# ProPrj_ftdi-jtag-xilinx_2025-03-20_v3_1.net
KiCad netlist of a schematic drawn in EasyEDA Pro
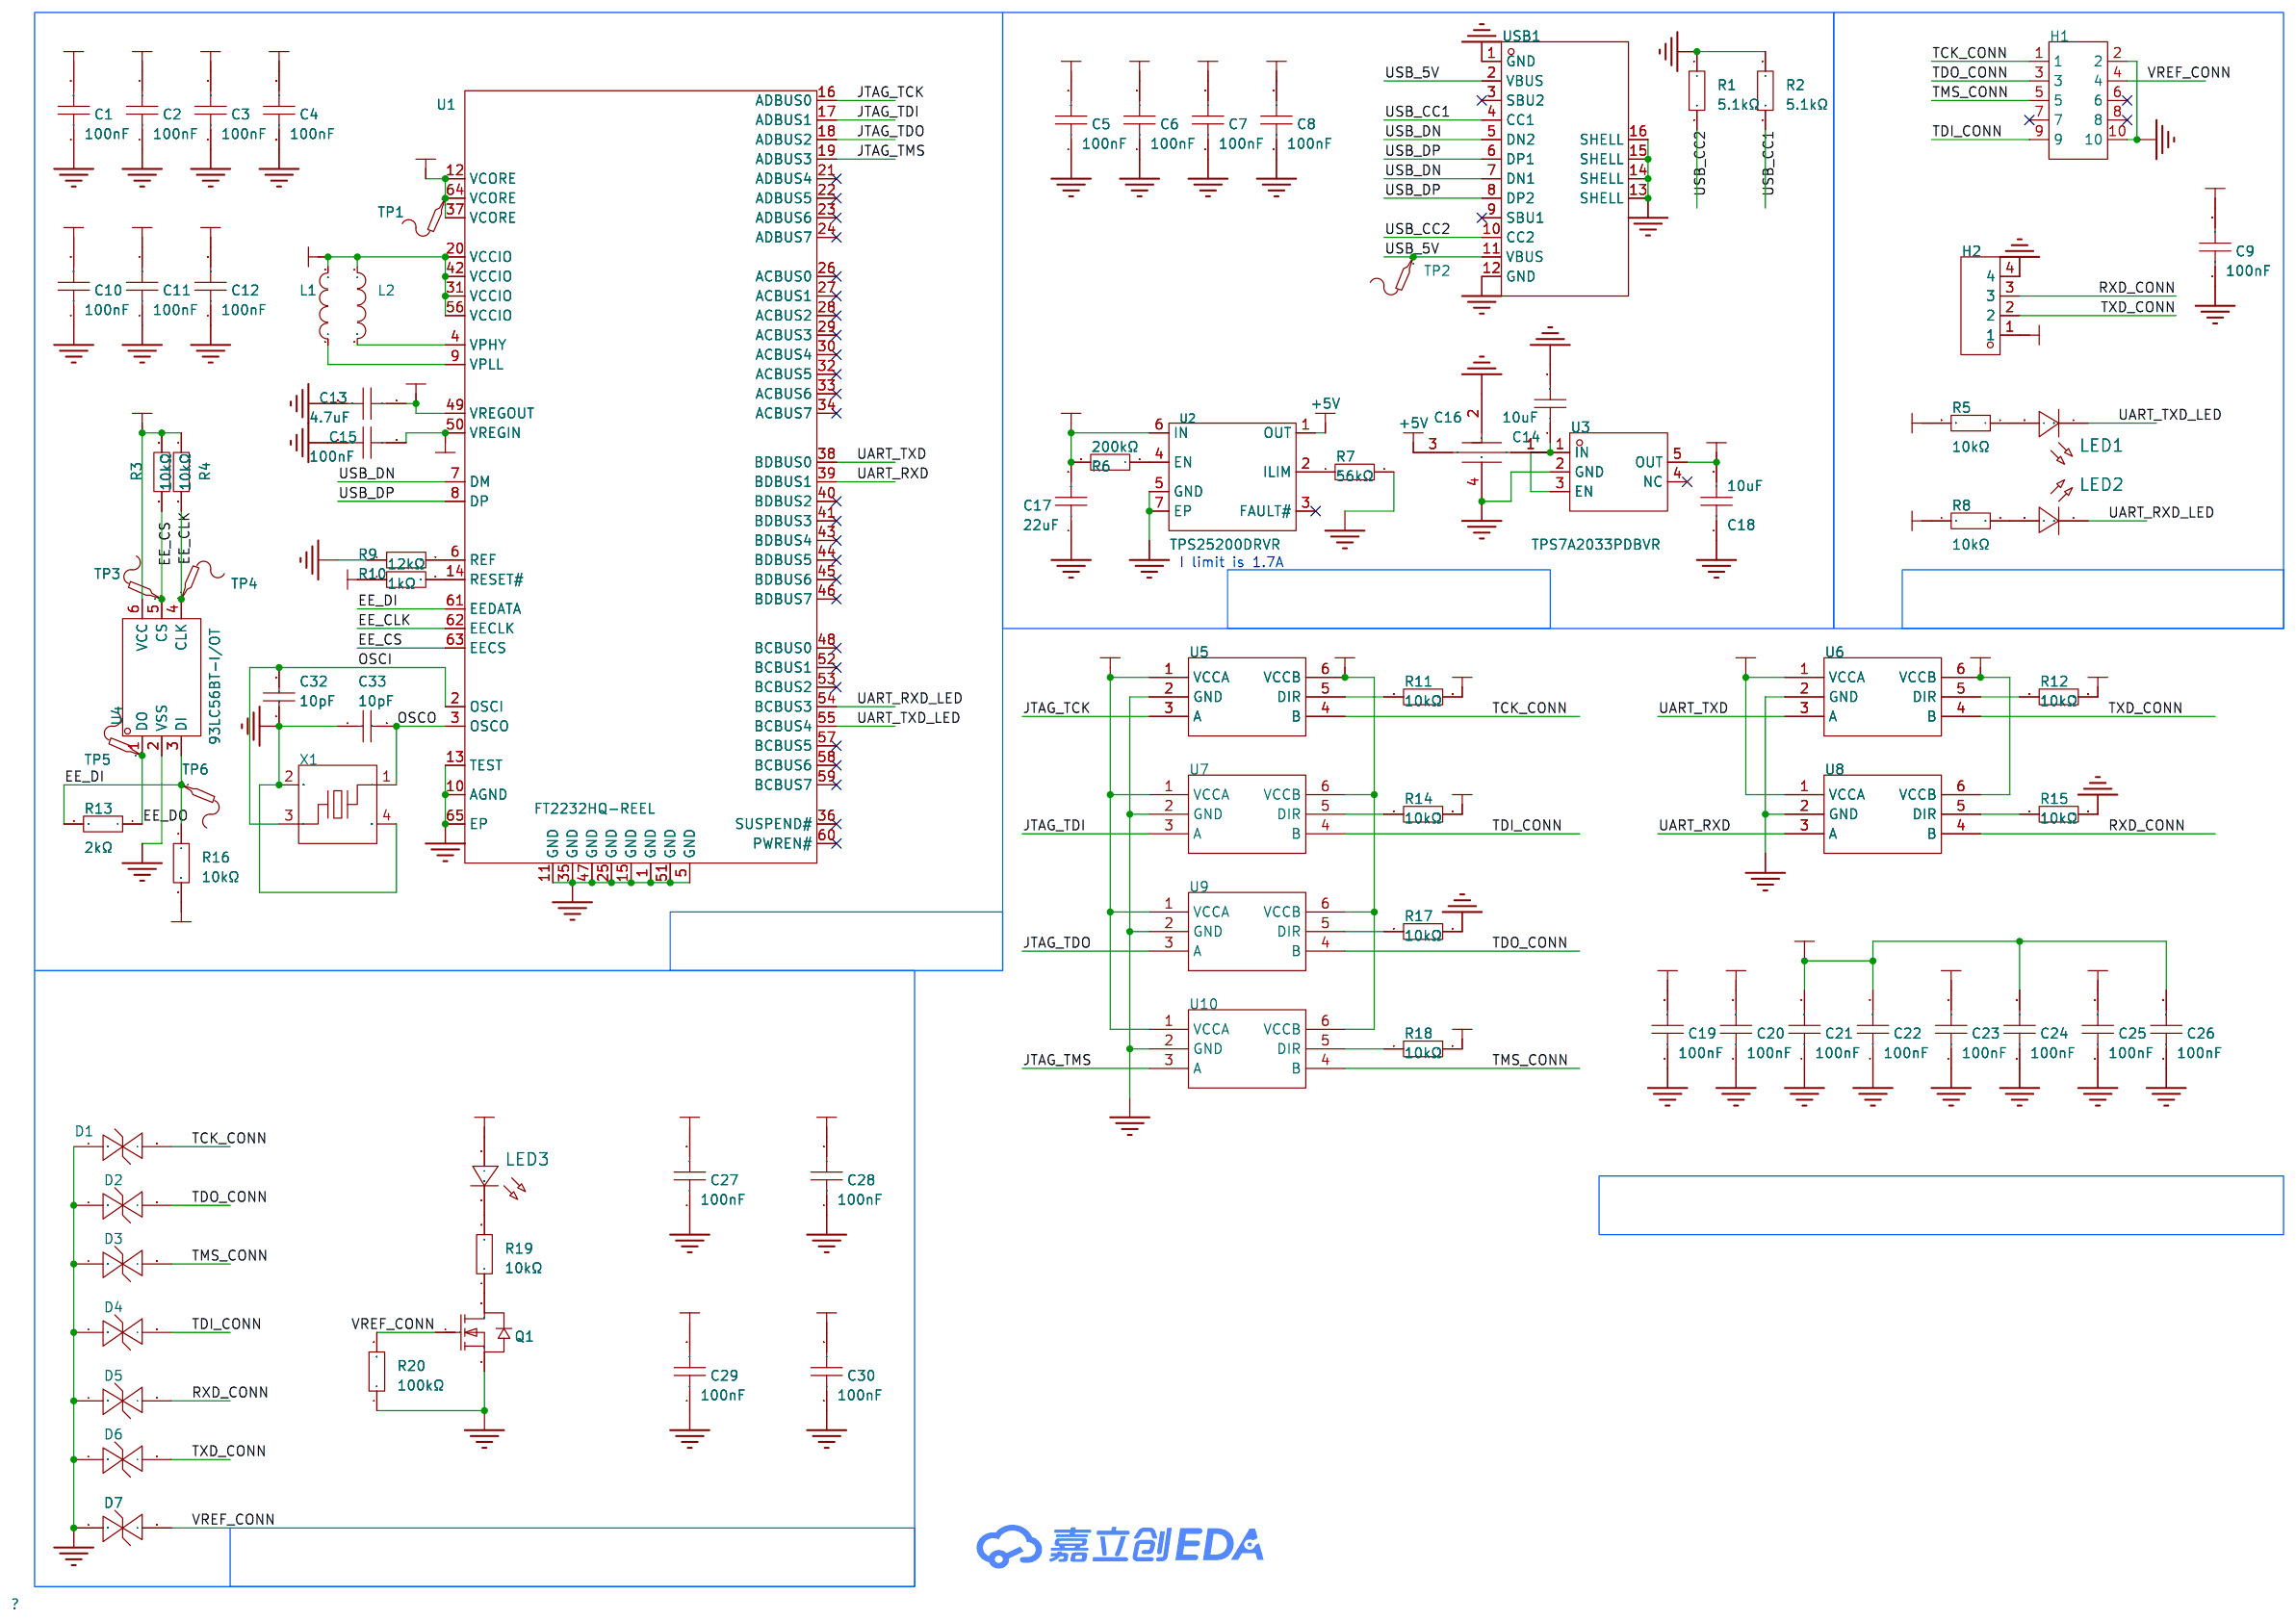
[diagram p0: schematic sheet]

(export (version "E")
  (design (tool "Eeschema 10.0.6"))
  (components
    (comp (ref "C1")
      (value "100nF")
      (footprint "easyedapro:C0603")
      (fields
        (field (name "Manufacturer Part") "CC0402KRX7R7BB104")
        (field (name "Manufacturer") "YAGEO(国巨)")
      )
      (libsource (lib "easyedapro") (part "CapAcitance"))
    )
    (comp (ref "C2")
      (value "100nF")
      (footprint "easyedapro:C0603")
      (fields
        (field (name "Manufacturer Part") "CC0402KRX7R7BB104")
        (field (name "Manufacturer") "YAGEO(国巨)")
      )
      (libsource (lib "easyedapro") (part "CapAcitance"))
    )
    (comp (ref "C3")
      (value "100nF")
      (footprint "easyedapro:C0603")
      (fields
        (field (name "Manufacturer Part") "CC0402KRX7R7BB104")
        (field (name "Manufacturer") "YAGEO(国巨)")
      )
      (libsource (lib "easyedapro") (part "CapAcitance"))
    )
    (comp (ref "C4")
      (value "100nF")
      (footprint "easyedapro:C0603")
      (fields
        (field (name "Manufacturer Part") "CC0402KRX7R7BB104")
        (field (name "Manufacturer") "YAGEO(国巨)")
      )
      (libsource (lib "easyedapro") (part "CapAcitance"))
    )
    (comp (ref "C5")
      (value "100nF")
      (footprint "easyedapro:C0603")
      (fields
        (field (name "Manufacturer Part") "CC0402KRX7R7BB104")
        (field (name "Manufacturer") "YAGEO(国巨)")
      )
      (libsource (lib "easyedapro") (part "CapAcitance"))
    )
    (comp (ref "C6")
      (value "100nF")
      (footprint "easyedapro:C0603")
      (fields
        (field (name "Manufacturer Part") "CC0402KRX7R7BB104")
        (field (name "Manufacturer") "YAGEO(国巨)")
      )
      (libsource (lib "easyedapro") (part "CapAcitance"))
    )
    (comp (ref "C7")
      (value "100nF")
      (footprint "easyedapro:C0603")
      (fields
        (field (name "Manufacturer Part") "CC0402KRX7R7BB104")
        (field (name "Manufacturer") "YAGEO(国巨)")
      )
      (libsource (lib "easyedapro") (part "CapAcitance"))
    )
    (comp (ref "C8")
      (value "100nF")
      (footprint "easyedapro:C0603")
      (fields
        (field (name "Manufacturer Part") "CC0402KRX7R7BB104")
        (field (name "Manufacturer") "YAGEO(国巨)")
      )
      (libsource (lib "easyedapro") (part "CapAcitance"))
    )
    (comp (ref "C9")
      (value "100nF")
      (footprint "easyedapro:C0603")
      (fields
        (field (name "Manufacturer Part") "CC0402KRX7R7BB104")
        (field (name "Manufacturer") "YAGEO(国巨)")
      )
      (libsource (lib "easyedapro") (part "CapAcitance"))
    )
    (comp (ref "C10")
      (value "100nF")
      (footprint "easyedapro:C0603")
      (fields
        (field (name "Manufacturer Part") "CC0402KRX7R7BB104")
        (field (name "Manufacturer") "YAGEO(国巨)")
      )
      (libsource (lib "easyedapro") (part "CapAcitance"))
    )
    (comp (ref "C11")
      (value "100nF")
      (footprint "easyedapro:C0603")
      (fields
        (field (name "Manufacturer Part") "CC0402KRX7R7BB104")
        (field (name "Manufacturer") "YAGEO(国巨)")
      )
      (libsource (lib "easyedapro") (part "CapAcitance"))
    )
    (comp (ref "C12")
      (value "100nF")
      (footprint "easyedapro:C0603")
      (fields
        (field (name "Manufacturer Part") "CC0402KRX7R7BB104")
        (field (name "Manufacturer") "YAGEO(国巨)")
      )
      (libsource (lib "easyedapro") (part "CapAcitance"))
    )
    (comp (ref "C13")
      (value "4.7uF")
      (footprint "easyedapro:C0603")
      (fields
        (field (name "Manufacturer Part") "CL05A475KP5NRNC")
        (field (name "Manufacturer") "SAMSUNG(三星)")
      )
      (libsource (lib "easyedapro") (part "CapAcitance"))
    )
    (comp (ref "C14")
      (value "10uF")
      (footprint "easyedapro:C0603")
      (fields
        (field (name "Manufacturer Part") "CL10A106MA8NRNC")
        (field (name "Manufacturer") "SAMSUNG(三星)")
      )
      (libsource (lib "easyedapro") (part "CapAcitance"))
    )
    (comp (ref "C15")
      (value "100nF")
      (footprint "easyedapro:C0603")
      (fields
        (field (name "Manufacturer Part") "CC0402KRX7R7BB104")
        (field (name "Manufacturer") "YAGEO(国巨)")
      )
      (libsource (lib "easyedapro") (part "CapAcitance"))
    )
    (comp (ref "C16")
      (value "NFM21PC104R1E3D")
      (footprint "easyedapro:CAP-SMD_4P-L2.0-W1.25")
      (description "电容量:100nF;精度:±20%;直流电阻:30mΩ;")
      (fields (field (name "Manufacturer") "muRata(村田)"))
      (libsource (lib "easyedapro") (part "NFM21PC104R1E3D"))
    )
    (comp (ref "C17")
      (value "22uF")
      (footprint "easyedapro:C0603")
      (fields
        (field (name "Manufacturer Part") "CGA0805X5R226M350MT")
        (field (name "Manufacturer") "HRE(芯声)")
      )
      (libsource (lib "easyedapro") (part "CapAcitance"))
    )
    (comp (ref "C18")
      (value "10uF")
      (footprint "easyedapro:C0603")
      (fields
        (field (name "Manufacturer Part") "CL10A106MA8NRNC")
        (field (name "Manufacturer") "SAMSUNG(三星)")
      )
      (libsource (lib "easyedapro") (part "CapAcitance"))
    )
    (comp (ref "C19")
      (value "100nF")
      (footprint "easyedapro:C0603")
      (fields
        (field (name "Manufacturer Part") "CC0402KRX7R7BB104")
        (field (name "Manufacturer") "YAGEO(国巨)")
      )
      (libsource (lib "easyedapro") (part "CapAcitance"))
    )
    (comp (ref "C20")
      (value "100nF")
      (footprint "easyedapro:C0603")
      (fields
        (field (name "Manufacturer Part") "CC0402KRX7R7BB104")
        (field (name "Manufacturer") "YAGEO(国巨)")
      )
      (libsource (lib "easyedapro") (part "CapAcitance"))
    )
    (comp (ref "C21")
      (value "100nF")
      (footprint "easyedapro:C0603")
      (fields
        (field (name "Manufacturer Part") "CC0402KRX7R7BB104")
        (field (name "Manufacturer") "YAGEO(国巨)")
      )
      (libsource (lib "easyedapro") (part "CapAcitance"))
    )
    (comp (ref "C22")
      (value "100nF")
      (footprint "easyedapro:C0603")
      (fields
        (field (name "Manufacturer Part") "CC0402KRX7R7BB104")
        (field (name "Manufacturer") "YAGEO(国巨)")
      )
      (libsource (lib "easyedapro") (part "CapAcitance"))
    )
    (comp (ref "C23")
      (value "100nF")
      (footprint "easyedapro:C0603")
      (fields
        (field (name "Manufacturer Part") "CC0402KRX7R7BB104")
        (field (name "Manufacturer") "YAGEO(国巨)")
      )
      (libsource (lib "easyedapro") (part "CapAcitance"))
    )
    (comp (ref "C24")
      (value "100nF")
      (footprint "easyedapro:C0603")
      (fields
        (field (name "Manufacturer Part") "CC0402KRX7R7BB104")
        (field (name "Manufacturer") "YAGEO(国巨)")
      )
      (libsource (lib "easyedapro") (part "CapAcitance"))
    )
    (comp (ref "C25")
      (value "100nF")
      (footprint "easyedapro:C0603")
      (fields
        (field (name "Manufacturer Part") "CC0402KRX7R7BB104")
        (field (name "Manufacturer") "YAGEO(国巨)")
      )
      (libsource (lib "easyedapro") (part "CapAcitance"))
    )
    (comp (ref "C26")
      (value "100nF")
      (footprint "easyedapro:C0603")
      (fields
        (field (name "Manufacturer Part") "CC0402KRX7R7BB104")
        (field (name "Manufacturer") "YAGEO(国巨)")
      )
      (libsource (lib "easyedapro") (part "CapAcitance"))
    )
    (comp (ref "C27")
      (value "100nF")
      (footprint "easyedapro:C0603")
      (fields
        (field (name "Manufacturer Part") "CC0402KRX7R7BB104")
        (field (name "Manufacturer") "YAGEO(国巨)")
      )
      (libsource (lib "easyedapro") (part "CapAcitance"))
    )
    (comp (ref "C28")
      (value "100nF")
      (footprint "easyedapro:C0603")
      (fields
        (field (name "Manufacturer Part") "CC0402KRX7R7BB104")
        (field (name "Manufacturer") "YAGEO(国巨)")
      )
      (libsource (lib "easyedapro") (part "CapAcitance"))
    )
    (comp (ref "C29")
      (value "100nF")
      (footprint "easyedapro:C0603")
      (fields
        (field (name "Manufacturer Part") "CC0402KRX7R7BB104")
        (field (name "Manufacturer") "YAGEO(国巨)")
      )
      (libsource (lib "easyedapro") (part "CapAcitance"))
    )
    (comp (ref "C30")
      (value "100nF")
      (footprint "easyedapro:C0603")
      (fields
        (field (name "Manufacturer Part") "CC0402KRX7R7BB104")
        (field (name "Manufacturer") "YAGEO(国巨)")
      )
      (libsource (lib "easyedapro") (part "CapAcitance"))
    )
    (comp (ref "C32")
      (value "10pF")
      (footprint "easyedapro:C0402")
      (description "容值:10pF;精度:±5%;额定电压:50V;材质(温度系数):NP0;")
      (fields
        (field (name "Manufacturer Part") "CC0402JRNPO9BN100")
        (field (name "Manufacturer") "YAGEO(国巨)")
      )
      (libsource (lib "easyedapro") (part "CC0402JRNPO9BN100"))
    )
    (comp (ref "C33")
      (value "10pF")
      (footprint "easyedapro:C0402")
      (description "容值:10pF;精度:±5%;额定电压:50V;材质(温度系数):NP0;")
      (fields
        (field (name "Manufacturer Part") "CC0402JRNPO9BN100")
        (field (name "Manufacturer") "YAGEO(国巨)")
      )
      (libsource (lib "easyedapro") (part "CC0402JRNPO9BN100"))
    )
    (comp (ref "D1")
      (value "H5VL10B")
      (footprint "easyedapro:SOD-882_L1.0-W0.6-BI")
      (description "极性:双向;反向截止电压(Vrwm):5V;最大钳位电压:10V;峰值脉冲电流(Ipp):5A;峰值脉冲功率(Ppp):50W;击穿电压:5.6V;")
      (fields (field (name "Manufacturer") "宏迦橙"))
      (libsource (lib "easyedapro") (part "H5VL10B"))
    )
    (comp (ref "D2")
      (value "H5VL10B")
      (footprint "easyedapro:SOD-882_L1.0-W0.6-BI")
      (description "极性:双向;反向截止电压(Vrwm):5V;最大钳位电压:10V;峰值脉冲电流(Ipp):5A;峰值脉冲功率(Ppp):50W;击穿电压:5.6V;")
      (fields (field (name "Manufacturer") "宏迦橙"))
      (libsource (lib "easyedapro") (part "H5VL10B"))
    )
    (comp (ref "D3")
      (value "H5VL10B")
      (footprint "easyedapro:SOD-882_L1.0-W0.6-BI")
      (description "极性:双向;反向截止电压(Vrwm):5V;最大钳位电压:10V;峰值脉冲电流(Ipp):5A;峰值脉冲功率(Ppp):50W;击穿电压:5.6V;")
      (fields (field (name "Manufacturer") "宏迦橙"))
      (libsource (lib "easyedapro") (part "H5VL10B"))
    )
    (comp (ref "D4")
      (value "H5VL10B")
      (footprint "easyedapro:SOD-882_L1.0-W0.6-BI")
      (description "极性:双向;反向截止电压(Vrwm):5V;最大钳位电压:10V;峰值脉冲电流(Ipp):5A;峰值脉冲功率(Ppp):50W;击穿电压:5.6V;")
      (fields (field (name "Manufacturer") "宏迦橙"))
      (libsource (lib "easyedapro") (part "H5VL10B"))
    )
    (comp (ref "D5")
      (value "H5VL10B")
      (footprint "easyedapro:SOD-882_L1.0-W0.6-BI")
      (description "极性:双向;反向截止电压(Vrwm):5V;最大钳位电压:10V;峰值脉冲电流(Ipp):5A;峰值脉冲功率(Ppp):50W;击穿电压:5.6V;")
      (fields (field (name "Manufacturer") "宏迦橙"))
      (libsource (lib "easyedapro") (part "H5VL10B"))
    )
    (comp (ref "D6")
      (value "H5VL10B")
      (footprint "easyedapro:SOD-882_L1.0-W0.6-BI")
      (description "极性:双向;反向截止电压(Vrwm):5V;最大钳位电压:10V;峰值脉冲电流(Ipp):5A;峰值脉冲功率(Ppp):50W;击穿电压:5.6V;")
      (fields (field (name "Manufacturer") "宏迦橙"))
      (libsource (lib "easyedapro") (part "H5VL10B"))
    )
    (comp (ref "D7")
      (value "H5VL10B")
      (footprint "easyedapro:SOD-882_L1.0-W0.6-BI")
      (description "极性:双向;反向截止电压(Vrwm):5V;最大钳位电压:10V;峰值脉冲电流(Ipp):5A;峰值脉冲功率(Ppp):50W;击穿电压:5.6V;")
      (fields (field (name "Manufacturer") "宏迦橙"))
      (libsource (lib "easyedapro") (part "H5VL10B"))
    )
    (comp (ref "H1")
      (value "PZ254-2-05-Z-8.5")
      (footprint "easyedapro:HDR-TH_10P-P2.54-V-M-R2-C5-S2.54")
      (fields (field (name "Manufacturer") "HCTL(华灿天禄)"))
      (libsource (lib "easyedapro") (part "PZ254-2-05-Z-8.5"))
    )
    (comp (ref "H2")
      (value "PZ254V-11-04P")
      (footprint "easyedapro:HDR-TH_4P-P2.54-V-M")
      (fields (field (name "Manufacturer") "XFCN(兴飞)"))
      (libsource (lib "easyedapro") (part "PZ254V-11-04P_C2691448"))
    )
    (comp (ref "L1")
      (value "BLM15PD121SN1D")
      (footprint "easyedapro:L0402")
      (description "标称阻抗@测试频率:120Ω@100MHz;误差:±25%;直流电阻(RDC):90mΩ;")
      (fields (field (name "Manufacturer") "muRata(村田)"))
      (libsource (lib "easyedapro") (part "BLM15PD121SN1D"))
    )
    (comp (ref "L2")
      (value "BLM15PD121SN1D")
      (footprint "easyedapro:L0402")
      (description "标称阻抗@测试频率:120Ω@100MHz;误差:±25%;直流电阻(RDC):90mΩ;")
      (fields (field (name "Manufacturer") "muRata(村田)"))
      (libsource (lib "easyedapro") (part "BLM15PD121SN1D"))
    )
    (comp (ref "LED1")
      (value "NCD0603Y1")
      (footprint "easyedapro:LED_0603")
      (fields (field (name "Manufacturer") "国星光电"))
      (libsource (lib "easyedapro") (part "LED_R"))
    )
    (comp (ref "LED2")
      (value "NCD0603Y1")
      (footprint "easyedapro:LED_0603")
      (fields (field (name "Manufacturer") "国星光电"))
      (libsource (lib "easyedapro") (part "LED_R"))
    )
    (comp (ref "LED3")
      (value "NCD0603Y1")
      (footprint "easyedapro:LED_0603")
      (fields (field (name "Manufacturer") "国星光电"))
      (libsource (lib "easyedapro") (part "LED_R"))
    )
    (comp (ref "Q1")
      (value "SI2302")
      (footprint "easyedapro:SOT-23-3_L2.9-W1.3-P1.90-LS2.4-BR")
      (description "类型:1个N沟道;漏源电压(Vdss):20V;连续漏极电流(Id):3A;导通电阻(RDS(on)):50mΩ@4.5V,3A;耗散功率(Pd):1W;阈值电压(Vgs(th)):1V;")
      (fields (field (name "Manufacturer") "YONGYUTAI(永裕泰)"))
      (libsource (lib "easyedapro") (part "SI2302_C2891732"))
    )
    (comp (ref "R1")
      (value "5.1kΩ")
      (footprint "easyedapro:R0603")
      (fields
        (field (name "Manufacturer Part") "0402WGF5101TCE")
        (field (name "Manufacturer") "UNI-ROYAL(厚声)")
      )
      (libsource (lib "easyedapro") (part "电阻"))
    )
    (comp (ref "R2")
      (value "5.1kΩ")
      (footprint "easyedapro:R0603")
      (fields
        (field (name "Manufacturer Part") "0402WGF5101TCE")
        (field (name "Manufacturer") "UNI-ROYAL(厚声)")
      )
      (libsource (lib "easyedapro") (part "电阻"))
    )
    (comp (ref "R3")
      (value "10kΩ")
      (footprint "easyedapro:R0603")
      (fields (field (name "Manufacturer Part") "RC0402FR-0710KL") (field (name "Manufacturer") "YAGEO(国巨)"))
      (libsource (lib "easyedapro") (part "电阻"))
    )
    (comp (ref "R4")
      (value "10kΩ")
      (footprint "easyedapro:R0603")
      (fields (field (name "Manufacturer Part") "RC0402FR-0710KL") (field (name "Manufacturer") "YAGEO(国巨)"))
      (libsource (lib "easyedapro") (part "电阻"))
    )
    (comp (ref "R5")
      (value "10kΩ")
      (footprint "easyedapro:R0603")
      (fields (field (name "Manufacturer Part") "RC0402FR-0710KL") (field (name "Manufacturer") "YAGEO(国巨)"))
      (libsource (lib "easyedapro") (part "电阻"))
    )
    (comp (ref "R6")
      (value "200kΩ")
      (footprint "easyedapro:R0603")
      (fields
        (field (name "Manufacturer Part") "0402WGF2003TCE")
        (field (name "Manufacturer") "UNI-ROYAL(厚声)")
      )
      (libsource (lib "easyedapro") (part "电阻"))
    )
    (comp (ref "R7")
      (value "56kΩ")
      (footprint "easyedapro:R0603")
      (fields
        (field (name "Manufacturer Part") "0402WGF5602TCE")
        (field (name "Manufacturer") "UNI-ROYAL(厚声)")
      )
      (libsource (lib "easyedapro") (part "电阻"))
    )
    (comp (ref "R8")
      (value "10kΩ")
      (footprint "easyedapro:R0603")
      (fields (field (name "Manufacturer Part") "RC0402FR-0710KL") (field (name "Manufacturer") "YAGEO(国巨)"))
      (libsource (lib "easyedapro") (part "电阻"))
    )
    (comp (ref "R9")
      (value "12kΩ")
      (footprint "easyedapro:R0603")
      (fields
        (field (name "Manufacturer Part") "0402WGF1202TCE")
        (field (name "Manufacturer") "UNI-ROYAL(厚声)")
      )
      (libsource (lib "easyedapro") (part "电阻"))
    )
    (comp (ref "R10")
      (value "1kΩ")
      (footprint "easyedapro:R0603")
      (fields
        (field (name "Manufacturer Part") "0402WGF1001TCE")
        (field (name "Manufacturer") "UNI-ROYAL(厚声)")
      )
      (libsource (lib "easyedapro") (part "电阻"))
    )
    (comp (ref "R11")
      (value "10kΩ")
      (footprint "easyedapro:R0603")
      (fields (field (name "Manufacturer Part") "RC0402FR-0710KL") (field (name "Manufacturer") "YAGEO(国巨)"))
      (libsource (lib "easyedapro") (part "电阻"))
    )
    (comp (ref "R12")
      (value "10kΩ")
      (footprint "easyedapro:R0603")
      (fields (field (name "Manufacturer Part") "RC0402FR-0710KL") (field (name "Manufacturer") "YAGEO(国巨)"))
      (libsource (lib "easyedapro") (part "电阻"))
    )
    (comp (ref "R13")
      (value "2kΩ")
      (footprint "easyedapro:R0603")
      (fields (field (name "Manufacturer Part") "FRC0402F2001TS") (field (name "Manufacturer") "FOJAN(富捷)"))
      (libsource (lib "easyedapro") (part "电阻"))
    )
    (comp (ref "R14")
      (value "10kΩ")
      (footprint "easyedapro:R0603")
      (fields (field (name "Manufacturer Part") "RC0402FR-0710KL") (field (name "Manufacturer") "YAGEO(国巨)"))
      (libsource (lib "easyedapro") (part "电阻"))
    )
    (comp (ref "R15")
      (value "10kΩ")
      (footprint "easyedapro:R0603")
      (fields (field (name "Manufacturer Part") "RC0402FR-0710KL") (field (name "Manufacturer") "YAGEO(国巨)"))
      (libsource (lib "easyedapro") (part "电阻"))
    )
    (comp (ref "R16")
      (value "10kΩ")
      (footprint "easyedapro:R0603")
      (fields (field (name "Manufacturer Part") "RC0402FR-0710KL") (field (name "Manufacturer") "YAGEO(国巨)"))
      (libsource (lib "easyedapro") (part "电阻"))
    )
    (comp (ref "R17")
      (value "10kΩ")
      (footprint "easyedapro:R0603")
      (fields (field (name "Manufacturer Part") "RC0402FR-0710KL") (field (name "Manufacturer") "YAGEO(国巨)"))
      (libsource (lib "easyedapro") (part "电阻"))
    )
    (comp (ref "R18")
      (value "10kΩ")
      (footprint "easyedapro:R0603")
      (fields (field (name "Manufacturer Part") "RC0402FR-0710KL") (field (name "Manufacturer") "YAGEO(国巨)"))
      (libsource (lib "easyedapro") (part "电阻"))
    )
    (comp (ref "R19")
      (value "10kΩ")
      (footprint "easyedapro:R0603")
      (fields (field (name "Manufacturer Part") "RC0402FR-0710KL") (field (name "Manufacturer") "YAGEO(国巨)"))
      (libsource (lib "easyedapro") (part "电阻"))
    )
    (comp (ref "R20")
      (value "100kΩ")
      (footprint "easyedapro:R0402")
      (description "电阻类型:厚膜电阻;阻值:100kΩ;精度:±1%;功率:62.5mW;最大工作电压:50V;温度系数:±100ppm/°C;")
      (fields
        (field (name "Manufacturer Part") "0402WGF1003TCE")
        (field (name "Manufacturer") "UNI-ROYAL(厚声)")
      )
      (libsource (lib "easyedapro") (part "0402WGF1003TCE"))
    )
    (comp (ref "TP1")
      (value "~")
      (footprint "easyedapro:Test-Point-0.5mm")
      (description "Test Point 测试点")
      (libsource (lib "easyedapro") (part "Test-Point"))
    )
    (comp (ref "TP2")
      (value "~")
      (footprint "easyedapro:Test-Point-0.5mm")
      (description "Test Point 测试点")
      (libsource (lib "easyedapro") (part "Test-Point"))
    )
    (comp (ref "TP3")
      (value "~")
      (footprint "easyedapro:Test-Point-0.5mm")
      (description "Test Point 测试点")
      (libsource (lib "easyedapro") (part "Test-Point"))
    )
    (comp (ref "TP4")
      (value "~")
      (footprint "easyedapro:Test-Point-0.5mm")
      (description "Test Point 测试点")
      (libsource (lib "easyedapro") (part "Test-Point"))
    )
    (comp (ref "TP5")
      (value "~")
      (footprint "easyedapro:Test-Point-0.5mm")
      (description "Test Point 测试点")
      (libsource (lib "easyedapro") (part "Test-Point"))
    )
    (comp (ref "TP6")
      (value "~")
      (footprint "easyedapro:Test-Point-0.5mm")
      (description "Test Point 测试点")
      (libsource (lib "easyedapro") (part "Test-Point"))
    )
    (comp (ref "U1")
      (value "FT2232HQ-REEL")
      (footprint "easyedapro:QFN-64_L9.0-W9.0-P0.50-TL-EP4.3")
      (description "应用功能:USB转UART；USB转FIFO;接口协议:UART;供电电压:3V~3.6V;")
      (fields (field (name "Manufacturer") "FTDI(飞特帝亚)"))
      (libsource (lib "easyedapro") (part "FT2232HQ-REEL"))
    )
    (comp (ref "U2")
      (value "TPS25200DRVR")
      (footprint "easyedapro:WSON-6_L2.0-W2.0-P0.65-TL-EP")
      (description "TPS25200 具有过压钳位的 6.5V/2.8A 电子保险丝")
      (fields (field (name "Manufacturer") "TI(德州仪器)"))
      (libsource (lib "easyedapro") (part "TPS25200DRVR"))
    )
    (comp (ref "U3")
      (value "TPS7A2033PDBVR")
      (footprint "easyedapro:SOT-23-5_L2.9-W1.6-P0.95-LS2.8-BR")
      (fields (field (name "Manufacturer") "TI(德州仪器)"))
      (libsource (lib "easyedapro") (part "TPS7A2033PDBVR"))
    )
    (comp (ref "U4")
      (value "93LC56BT-I/OT")
      (footprint "easyedapro:SOT-23-6_L2.9-W1.6-P0.95-LS2.8-BR")
      (fields (field (name "Manufacturer") "MICROCHIP(美国微芯)"))
      (libsource (lib "easyedapro") (part "93LC56BT-I/OT"))
    )
    (comp (ref "U5")
      (value "SN74LVC1T45DBVR")
      (footprint "easyedapro:SOT-23-6_L2.9-W1.6-P0.95-LS2.8-BR")
      (description "数据速率:420Mbps;电压(VCCA):1.65V~5.5V;电压(VCCB):1.65V~5.5V;电路数:1;每个电路通道数:1;")
      (fields (field (name "Manufacturer") "TI(德州仪器)"))
      (libsource (lib "easyedapro") (part "SN74LVC1T45DBVR"))
    )
    (comp (ref "U6")
      (value "SN74LVC1T45DBVR")
      (footprint "easyedapro:SOT-23-6_L2.9-W1.6-P0.95-LS2.8-BR")
      (description "数据速率:420Mbps;电压(VCCA):1.65V~5.5V;电压(VCCB):1.65V~5.5V;电路数:1;每个电路通道数:1;")
      (fields (field (name "Manufacturer") "TI(德州仪器)"))
      (libsource (lib "easyedapro") (part "SN74LVC1T45DBVR"))
    )
    (comp (ref "U7")
      (value "SN74LVC1T45DBVR")
      (footprint "easyedapro:SOT-23-6_L2.9-W1.6-P0.95-LS2.8-BR")
      (description "数据速率:420Mbps;电压(VCCA):1.65V~5.5V;电压(VCCB):1.65V~5.5V;电路数:1;每个电路通道数:1;")
      (fields (field (name "Manufacturer") "TI(德州仪器)"))
      (libsource (lib "easyedapro") (part "SN74LVC1T45DBVR"))
    )
    (comp (ref "U8")
      (value "SN74LVC1T45DBVR")
      (footprint "easyedapro:SOT-23-6_L2.9-W1.6-P0.95-LS2.8-BR")
      (description "数据速率:420Mbps;电压(VCCA):1.65V~5.5V;电压(VCCB):1.65V~5.5V;电路数:1;每个电路通道数:1;")
      (fields (field (name "Manufacturer") "TI(德州仪器)"))
      (libsource (lib "easyedapro") (part "SN74LVC1T45DBVR"))
    )
    (comp (ref "U9")
      (value "SN74LVC1T45DBVR")
      (footprint "easyedapro:SOT-23-6_L2.9-W1.6-P0.95-LS2.8-BR")
      (description "数据速率:420Mbps;电压(VCCA):1.65V~5.5V;电压(VCCB):1.65V~5.5V;电路数:1;每个电路通道数:1;")
      (fields (field (name "Manufacturer") "TI(德州仪器)"))
      (libsource (lib "easyedapro") (part "SN74LVC1T45DBVR"))
    )
    (comp (ref "U10")
      (value "SN74LVC1T45DBVR")
      (footprint "easyedapro:SOT-23-6_L2.9-W1.6-P0.95-LS2.8-BR")
      (description "数据速率:420Mbps;电压(VCCA):1.65V~5.5V;电压(VCCB):1.65V~5.5V;电路数:1;每个电路通道数:1;")
      (fields (field (name "Manufacturer") "TI(德州仪器)"))
      (libsource (lib "easyedapro") (part "SN74LVC1T45DBVR"))
    )
    (comp (ref "USB1")
      (value "TYPEC-302-BRP16SC16")
      (footprint "easyedapro:USB-C-SMD_TYPEC-302-BRP16SC16")
      (fields (field (name "Manufacturer") "XUNPU(讯普)"))
      (libsource (lib "easyedapro") (part "TYPEC-302-BRP16SC16"))
    )
    (comp (ref "X1")
      (value "12MHz")
      (footprint "easyedapro:CRYSTAL-SMD_4P-L2.5-W2.0-BL-A")
      (description "晶振类型:贴片晶振;频率:12MHz;常温频差:±10ppm;负载电容:10pF;频率稳定度:±20ppm;")
      (fields (field (name "Manufacturer Part") "X252012MMB4SI-24") (field (name "Manufacturer") "YXC(扬兴晶振)"))
      (libsource (lib "easyedapro") (part "X252012MMB4SI-24"))
    )
  )
  (nets
    (net (code "1") (name "+5V") (class "Default")
      (node (ref "C16") (pin "3") (pinfunction "OUT_3") (pintype "input"))
      (node (ref "U2") (pin "1") (pinfunction "OUT_1") (pintype "input"))
    )
    (net (code "2") (name "/EE_CLK") (class "Default")
      (node (ref "R4") (pin "2") (pinfunction "2_2") (pintype "input"))
      (node (ref "TP4") (pin "1") (pinfunction "1_1") (pintype "input"))
      (node (ref "U1") (pin "62") (pinfunction "EECLK_62") (pintype "input"))
      (node (ref "U4") (pin "4") (pinfunction "CLK_4") (pintype "input"))
    )
    (net (code "3") (name "/EE_CS") (class "Default")
      (node (ref "R3") (pin "2") (pinfunction "2_2") (pintype "input"))
      (node (ref "TP3") (pin "1") (pinfunction "1_1") (pintype "input"))
      (node (ref "U1") (pin "63") (pinfunction "EECS_63") (pintype "input"))
      (node (ref "U4") (pin "5") (pinfunction "CS_5") (pintype "input"))
    )
    (net (code "4") (name "/EE_DI") (class "Default")
      (node (ref "R13") (pin "2") (pinfunction "2_2") (pintype "input"))
      (node (ref "R16") (pin "1") (pinfunction "1_1") (pintype "input"))
      (node (ref "TP6") (pin "1") (pinfunction "1_1") (pintype "input"))
      (node (ref "U1") (pin "61") (pinfunction "EEDATA_61") (pintype "input"))
      (node (ref "U4") (pin "3") (pinfunction "DI_3") (pintype "input"))
    )
    (net (code "5") (name "/EE_DO") (class "Default")
      (node (ref "R13") (pin "1") (pinfunction "1_1") (pintype "input"))
      (node (ref "TP5") (pin "1") (pinfunction "1_1") (pintype "input"))
      (node (ref "U4") (pin "1") (pinfunction "DO_1") (pintype "input"))
    )
    (net (code "6") (name "/JTAG_TCK") (class "Default")
      (node (ref "U1") (pin "16") (pinfunction "ADBUS0_16") (pintype "input"))
      (node (ref "U5") (pin "3") (pinfunction "A_3") (pintype "unspecified"))
    )
    (net (code "7") (name "/JTAG_TDI") (class "Default")
      (node (ref "U1") (pin "17") (pinfunction "ADBUS1_17") (pintype "input"))
      (node (ref "U7") (pin "3") (pinfunction "A_3") (pintype "unspecified"))
    )
    (net (code "8") (name "/JTAG_TDO") (class "Default")
      (node (ref "U1") (pin "18") (pinfunction "ADBUS2_18") (pintype "input"))
      (node (ref "U9") (pin "3") (pinfunction "A_3") (pintype "unspecified"))
    )
    (net (code "9") (name "/JTAG_TMS") (class "Default")
      (node (ref "U1") (pin "19") (pinfunction "ADBUS3_19") (pintype "input"))
      (node (ref "U10") (pin "3") (pinfunction "A_3") (pintype "unspecified"))
    )
    (net (code "10") (name "/OSCI") (class "Default")
      (node (ref "C32") (pin "2") (pinfunction "2_2") (pintype "input"))
      (node (ref "U1") (pin "2") (pinfunction "OSCI_2") (pintype "input"))
      (node (ref "X1") (pin "3") (pinfunction "3_3") (pintype "input"))
    )
    (net (code "11") (name "/OSCO") (class "Default")
      (node (ref "C33") (pin "2") (pinfunction "2_2") (pintype "input"))
      (node (ref "U1") (pin "3") (pinfunction "OSCO_3") (pintype "input"))
      (node (ref "X1") (pin "1") (pinfunction "1_1") (pintype "input"))
    )
    (net (code "12") (name "/RXD_CONN") (class "Default")
      (node (ref "D5") (pin "2") (pinfunction "A_2") (pintype "unspecified"))
      (node (ref "H2") (pin "3") (pinfunction "3_3") (pintype "unspecified"))
      (node (ref "U8") (pin "4") (pinfunction "B_4") (pintype "unspecified"))
    )
    (net (code "13") (name "/TCK_CONN") (class "Default")
      (node (ref "D1") (pin "2") (pinfunction "A_2") (pintype "unspecified"))
      (node (ref "H1") (pin "1") (pinfunction "1_1") (pintype "unspecified"))
      (node (ref "U5") (pin "4") (pinfunction "B_4") (pintype "unspecified"))
    )
    (net (code "14") (name "/TDI_CONN") (class "Default")
      (node (ref "D4") (pin "2") (pinfunction "A_2") (pintype "unspecified"))
      (node (ref "H1") (pin "9") (pinfunction "9_9") (pintype "unspecified"))
      (node (ref "U7") (pin "4") (pinfunction "B_4") (pintype "unspecified"))
    )
    (net (code "15") (name "/TDO_CONN") (class "Default")
      (node (ref "D2") (pin "2") (pinfunction "A_2") (pintype "unspecified"))
      (node (ref "H1") (pin "3") (pinfunction "3_3") (pintype "unspecified"))
      (node (ref "U9") (pin "4") (pinfunction "B_4") (pintype "unspecified"))
    )
    (net (code "16") (name "/TMS_CONN") (class "Default")
      (node (ref "D3") (pin "2") (pinfunction "A_2") (pintype "unspecified"))
      (node (ref "H1") (pin "5") (pinfunction "5_5") (pintype "unspecified"))
      (node (ref "U10") (pin "4") (pinfunction "B_4") (pintype "unspecified"))
    )
    (net (code "17") (name "/TXD_CONN") (class "Default")
      (node (ref "D6") (pin "2") (pinfunction "A_2") (pintype "unspecified"))
      (node (ref "H2") (pin "2") (pinfunction "2_2") (pintype "unspecified"))
      (node (ref "U6") (pin "4") (pinfunction "B_4") (pintype "unspecified"))
    )
    (net (code "18") (name "/UART_RXD") (class "Default")
      (node (ref "U1") (pin "39") (pinfunction "BDBUS1_39") (pintype "input"))
      (node (ref "U8") (pin "3") (pinfunction "A_3") (pintype "unspecified"))
    )
    (net (code "19") (name "/UART_RXD_LED") (class "Default")
      (node (ref "LED2") (pin "1") (pinfunction "C_1") (pintype "input"))
      (node (ref "U1") (pin "54") (pinfunction "BCBUS3_54") (pintype "input"))
    )
    (net (code "20") (name "/UART_TXD") (class "Default")
      (node (ref "U1") (pin "38") (pinfunction "BDBUS0_38") (pintype "input"))
      (node (ref "U6") (pin "3") (pinfunction "A_3") (pintype "unspecified"))
    )
    (net (code "21") (name "/UART_TXD_LED") (class "Default")
      (node (ref "LED1") (pin "1") (pinfunction "C_1") (pintype "input"))
      (node (ref "U1") (pin "55") (pinfunction "BCBUS4_55") (pintype "input"))
    )
    (net (code "22") (name "/USB_CC1") (class "Default")
      (node (ref "R2") (pin "2") (pinfunction "2_2") (pintype "input"))
      (node (ref "USB1") (pin "4") (pinfunction "CC1_4") (pintype "unspecified"))
    )
    (net (code "23") (name "/USB_CC2") (class "Default")
      (node (ref "R1") (pin "2") (pinfunction "2_2") (pintype "input"))
      (node (ref "USB1") (pin "10") (pinfunction "CC2_10") (pintype "unspecified"))
    )
    (net (code "24") (name "/USB_DN") (class "Default")
      (node (ref "U1") (pin "7") (pinfunction "DM_7") (pintype "input"))
      (node (ref "USB1") (pin "5") (pinfunction "DN2_5") (pintype "unspecified"))
      (node (ref "USB1") (pin "7") (pinfunction "DN1_7") (pintype "unspecified"))
    )
    (net (code "25") (name "/USB_DP") (class "Default")
      (node (ref "U1") (pin "8") (pinfunction "DP_8") (pintype "input"))
      (node (ref "USB1") (pin "6") (pinfunction "DP1_6") (pintype "unspecified"))
      (node (ref "USB1") (pin "8") (pinfunction "DP2_8") (pintype "unspecified"))
    )
    (net (code "26") (name "3V3") (class "Default")
      (node (ref "C1") (pin "2") (pinfunction "2_2") (pintype "input"))
      (node (ref "C15") (pin "2") (pinfunction "2_2") (pintype "input"))
      (node (ref "C18") (pin "2") (pinfunction "2_2") (pintype "input"))
      (node (ref "C19") (pin "2") (pinfunction "2_2") (pintype "input"))
      (node (ref "C2") (pin "2") (pinfunction "2_2") (pintype "input"))
      (node (ref "C20") (pin "2") (pinfunction "2_2") (pintype "input"))
      (node (ref "C23") (pin "2") (pinfunction "2_2") (pintype "input"))
      (node (ref "C25") (pin "2") (pinfunction "2_2") (pintype "input"))
      (node (ref "C27") (pin "2") (pinfunction "2_2") (pintype "input"))
      (node (ref "C29") (pin "2") (pinfunction "2_2") (pintype "input"))
      (node (ref "C3") (pin "2") (pinfunction "2_2") (pintype "input"))
      (node (ref "C4") (pin "2") (pinfunction "2_2") (pintype "input"))
      (node (ref "C5") (pin "2") (pinfunction "2_2") (pintype "input"))
      (node (ref "C6") (pin "2") (pinfunction "2_2") (pintype "input"))
      (node (ref "C7") (pin "2") (pinfunction "2_2") (pintype "input"))
      (node (ref "C8") (pin "2") (pinfunction "2_2") (pintype "input"))
      (node (ref "H2") (pin "1") (pinfunction "1_1") (pintype "unspecified"))
      (node (ref "L1") (pin "2") (pinfunction "2_2") (pintype "input"))
      (node (ref "L2") (pin "1") (pinfunction "1_1") (pintype "input"))
      (node (ref "LED3") (pin "2") (pinfunction "A_2") (pintype "input"))
      (node (ref "R10") (pin "1") (pinfunction "1_1") (pintype "input"))
      (node (ref "R11") (pin "2") (pinfunction "2_2") (pintype "input"))
      (node (ref "R12") (pin "2") (pinfunction "2_2") (pintype "input"))
      (node (ref "R14") (pin "2") (pinfunction "2_2") (pintype "input"))
      (node (ref "R16") (pin "2") (pinfunction "2_2") (pintype "input"))
      (node (ref "R18") (pin "2") (pinfunction "2_2") (pintype "input"))
      (node (ref "R3") (pin "1") (pinfunction "1_1") (pintype "input"))
      (node (ref "R4") (pin "1") (pinfunction "1_1") (pintype "input"))
      (node (ref "R5") (pin "2") (pinfunction "2_2") (pintype "input"))
      (node (ref "R8") (pin "1") (pinfunction "1_1") (pintype "input"))
      (node (ref "U1") (pin "20") (pinfunction "VCCIO_20") (pintype "input"))
      (node (ref "U1") (pin "31") (pinfunction "VCCIO_31") (pintype "input"))
      (node (ref "U1") (pin "42") (pinfunction "VCCIO_42") (pintype "input"))
      (node (ref "U1") (pin "50") (pinfunction "VREGIN_50") (pintype "input"))
      (node (ref "U1") (pin "56") (pinfunction "VCCIO_56") (pintype "input"))
      (node (ref "U10") (pin "1") (pinfunction "VCCA_1") (pintype "unspecified"))
      (node (ref "U3") (pin "5") (pinfunction "OUT_5") (pintype "input"))
      (node (ref "U4") (pin "6") (pinfunction "VCC_6") (pintype "input"))
      (node (ref "U5") (pin "1") (pinfunction "VCCA_1") (pintype "unspecified"))
      (node (ref "U6") (pin "1") (pinfunction "VCCA_1") (pintype "unspecified"))
      (node (ref "U7") (pin "1") (pinfunction "VCCA_1") (pintype "unspecified"))
      (node (ref "U8") (pin "1") (pinfunction "VCCA_1") (pintype "unspecified"))
      (node (ref "U9") (pin "1") (pinfunction "VCCA_1") (pintype "unspecified"))
    )
    (net (code "27") (name "GND") (class "Default")
      (node (ref "C1") (pin "1") (pinfunction "1_1") (pintype "input"))
      (node (ref "C10") (pin "1") (pinfunction "1_1") (pintype "input"))
      (node (ref "C11") (pin "1") (pinfunction "1_1") (pintype "input"))
      (node (ref "C12") (pin "1") (pinfunction "1_1") (pintype "input"))
      (node (ref "C13") (pin "2") (pinfunction "2_2") (pintype "input"))
      (node (ref "C14") (pin "2") (pinfunction "2_2") (pintype "input"))
      (node (ref "C15") (pin "1") (pinfunction "1_1") (pintype "input"))
      (node (ref "C16") (pin "2") (pinfunction "GND_2") (pintype "input"))
      (node (ref "C16") (pin "4") (pinfunction "GND_4") (pintype "input"))
      (node (ref "C17") (pin "1") (pinfunction "1_1") (pintype "input"))
      (node (ref "C18") (pin "1") (pinfunction "1_1") (pintype "input"))
      (node (ref "C19") (pin "1") (pinfunction "1_1") (pintype "input"))
      (node (ref "C2") (pin "1") (pinfunction "1_1") (pintype "input"))
      (node (ref "C20") (pin "1") (pinfunction "1_1") (pintype "input"))
      (node (ref "C21") (pin "1") (pinfunction "1_1") (pintype "input"))
      (node (ref "C22") (pin "1") (pinfunction "1_1") (pintype "input"))
      (node (ref "C23") (pin "1") (pinfunction "1_1") (pintype "input"))
      (node (ref "C24") (pin "1") (pinfunction "1_1") (pintype "input"))
      (node (ref "C25") (pin "1") (pinfunction "1_1") (pintype "input"))
      (node (ref "C26") (pin "1") (pinfunction "1_1") (pintype "input"))
      (node (ref "C27") (pin "1") (pinfunction "1_1") (pintype "input"))
      (node (ref "C28") (pin "1") (pinfunction "1_1") (pintype "input"))
      (node (ref "C29") (pin "1") (pinfunction "1_1") (pintype "input"))
      (node (ref "C3") (pin "1") (pinfunction "1_1") (pintype "input"))
      (node (ref "C30") (pin "1") (pinfunction "1_1") (pintype "input"))
      (node (ref "C32") (pin "1") (pinfunction "1_1") (pintype "input"))
      (node (ref "C33") (pin "1") (pinfunction "1_1") (pintype "input"))
      (node (ref "C4") (pin "1") (pinfunction "1_1") (pintype "input"))
      (node (ref "C5") (pin "1") (pinfunction "1_1") (pintype "input"))
      (node (ref "C6") (pin "1") (pinfunction "1_1") (pintype "input"))
      (node (ref "C7") (pin "1") (pinfunction "1_1") (pintype "input"))
      (node (ref "C8") (pin "1") (pinfunction "1_1") (pintype "input"))
      (node (ref "C9") (pin "1") (pinfunction "1_1") (pintype "input"))
      (node (ref "D1") (pin "1") (pinfunction "C_1") (pintype "unspecified"))
      (node (ref "D2") (pin "1") (pinfunction "C_1") (pintype "unspecified"))
      (node (ref "D3") (pin "1") (pinfunction "C_1") (pintype "unspecified"))
      (node (ref "D4") (pin "1") (pinfunction "C_1") (pintype "unspecified"))
      (node (ref "D5") (pin "1") (pinfunction "C_1") (pintype "unspecified"))
      (node (ref "D6") (pin "1") (pinfunction "C_1") (pintype "unspecified"))
      (node (ref "D7") (pin "1") (pinfunction "C_1") (pintype "unspecified"))
      (node (ref "H1") (pin "10") (pinfunction "10_10") (pintype "unspecified"))
      (node (ref "H1") (pin "2") (pinfunction "2_2") (pintype "unspecified"))
      (node (ref "H2") (pin "4") (pinfunction "4_4") (pintype "unspecified"))
      (node (ref "Q1") (pin "2") (pinfunction "S_2") (pintype "unspecified"))
      (node (ref "R1") (pin "1") (pinfunction "1_1") (pintype "input"))
      (node (ref "R15") (pin "2") (pinfunction "2_2") (pintype "input"))
      (node (ref "R17") (pin "2") (pinfunction "2_2") (pintype "input"))
      (node (ref "R2") (pin "1") (pinfunction "1_1") (pintype "input"))
      (node (ref "R20") (pin "1") (pinfunction "1_1") (pintype "input"))
      (node (ref "R7") (pin "2") (pinfunction "2_2") (pintype "input"))
      (node (ref "R9") (pin "1") (pinfunction "1_1") (pintype "input"))
      (node (ref "U1") (pin "1") (pinfunction "GND_1") (pintype "input"))
      (node (ref "U1") (pin "10") (pinfunction "AGND_10") (pintype "input"))
      (node (ref "U1") (pin "11") (pinfunction "GND_11") (pintype "input"))
      (node (ref "U1") (pin "13") (pinfunction "TEST_13") (pintype "input"))
      (node (ref "U1") (pin "15") (pinfunction "GND_15") (pintype "input"))
      (node (ref "U1") (pin "25") (pinfunction "GND_25") (pintype "input"))
      (node (ref "U1") (pin "35") (pinfunction "GND_35") (pintype "input"))
      (node (ref "U1") (pin "47") (pinfunction "GND_47") (pintype "input"))
      (node (ref "U1") (pin "5") (pinfunction "GND_5") (pintype "input"))
      (node (ref "U1") (pin "51") (pinfunction "GND_51") (pintype "input"))
      (node (ref "U1") (pin "65") (pinfunction "EP_65") (pintype "input"))
      (node (ref "U10") (pin "2") (pinfunction "GND_2") (pintype "unspecified"))
      (node (ref "U2") (pin "5") (pinfunction "GND_5") (pintype "input"))
      (node (ref "U2") (pin "7") (pinfunction "EP_7") (pintype "input"))
      (node (ref "U3") (pin "2") (pinfunction "GND_2") (pintype "input"))
      (node (ref "U4") (pin "2") (pinfunction "VSS_2") (pintype "input"))
      (node (ref "U5") (pin "2") (pinfunction "GND_2") (pintype "unspecified"))
      (node (ref "U6") (pin "2") (pinfunction "GND_2") (pintype "unspecified"))
      (node (ref "U7") (pin "2") (pinfunction "GND_2") (pintype "unspecified"))
      (node (ref "U8") (pin "2") (pinfunction "GND_2") (pintype "unspecified"))
      (node (ref "U9") (pin "2") (pinfunction "GND_2") (pintype "unspecified"))
      (node (ref "USB1") (pin "1") (pinfunction "GND_1") (pintype "unspecified"))
      (node (ref "USB1") (pin "12") (pinfunction "GND_12") (pintype "unspecified"))
      (node (ref "USB1") (pin "13") (pinfunction "SHELL_13") (pintype "unspecified"))
      (node (ref "USB1") (pin "14") (pinfunction "SHELL_14") (pintype "unspecified"))
      (node (ref "USB1") (pin "15") (pinfunction "SHELL_15") (pintype "unspecified"))
      (node (ref "USB1") (pin "16") (pinfunction "SHELL_16") (pintype "unspecified"))
      (node (ref "X1") (pin "2") (pinfunction "GND_2") (pintype "input"))
      (node (ref "X1") (pin "4") (pinfunction "GND_4") (pintype "input"))
    )
    (net (code "28") (name "Net-(C16-IN)") (class "Default")
      (node (ref "C14") (pin "1") (pinfunction "1_1") (pintype "input"))
      (node (ref "C16") (pin "1") (pinfunction "IN_1") (pintype "input"))
      (node (ref "U3") (pin "1") (pinfunction "IN_1") (pintype "input"))
      (node (ref "U3") (pin "3") (pinfunction "EN_3") (pintype "input"))
    )
    (net (code "29") (name "Net-(LED1-A)") (class "Default")
      (node (ref "LED1") (pin "2") (pinfunction "A_2") (pintype "input"))
      (node (ref "R5") (pin "1") (pinfunction "1_1") (pintype "input"))
    )
    (net (code "30") (name "Net-(LED2-A)") (class "Default")
      (node (ref "LED2") (pin "2") (pinfunction "A_2") (pintype "input"))
      (node (ref "R8") (pin "2") (pinfunction "2_2") (pintype "input"))
    )
    (net (code "31") (name "Net-(LED3-C)") (class "Default")
      (node (ref "LED3") (pin "1") (pinfunction "C_1") (pintype "input"))
      (node (ref "R19") (pin "2") (pinfunction "2_2") (pintype "input"))
    )
    (net (code "32") (name "Net-(Q1-D)") (class "Default")
      (node (ref "Q1") (pin "3") (pinfunction "D_3") (pintype "unspecified"))
      (node (ref "R19") (pin "1") (pinfunction "1_1") (pintype "input"))
    )
    (net (code "33") (name "Net-(U1-REF)") (class "Default")
      (node (ref "R9") (pin "2") (pinfunction "2_2") (pintype "input"))
      (node (ref "U1") (pin "6") (pinfunction "REF_6") (pintype "input"))
    )
    (net (code "34") (name "Net-(U1-RESET#)") (class "Default")
      (node (ref "R10") (pin "2") (pinfunction "2_2") (pintype "input"))
      (node (ref "U1") (pin "14") (pinfunction "RESET#_14") (pintype "input"))
    )
    (net (code "35") (name "Net-(U1-VPHY)") (class "Default")
      (node (ref "L2") (pin "2") (pinfunction "2_2") (pintype "input"))
      (node (ref "U1") (pin "4") (pinfunction "VPHY_4") (pintype "input"))
    )
    (net (code "36") (name "Net-(U1-VPLL)") (class "Default")
      (node (ref "L1") (pin "1") (pinfunction "1_1") (pintype "input"))
      (node (ref "U1") (pin "9") (pinfunction "VPLL_9") (pintype "input"))
    )
    (net (code "37") (name "Net-(U2-EN)") (class "Default")
      (node (ref "R6") (pin "1") (pinfunction "1_1") (pintype "input"))
      (node (ref "U2") (pin "4") (pinfunction "EN_4") (pintype "input"))
    )
    (net (code "38") (name "Net-(U2-ILIM)") (class "Default")
      (node (ref "R7") (pin "1") (pinfunction "1_1") (pintype "input"))
      (node (ref "U2") (pin "2") (pinfunction "ILIM_2") (pintype "input"))
    )
    (net (code "39") (name "Net-(U5-DIR)") (class "Default")
      (node (ref "R11") (pin "1") (pinfunction "1_1") (pintype "input"))
      (node (ref "U5") (pin "5") (pinfunction "DIR_5") (pintype "unspecified"))
    )
    (net (code "40") (name "Net-(U6-DIR)") (class "Default")
      (node (ref "R12") (pin "1") (pinfunction "1_1") (pintype "input"))
      (node (ref "U6") (pin "5") (pinfunction "DIR_5") (pintype "unspecified"))
    )
    (net (code "41") (name "Net-(U7-DIR)") (class "Default")
      (node (ref "R14") (pin "1") (pinfunction "1_1") (pintype "input"))
      (node (ref "U7") (pin "5") (pinfunction "DIR_5") (pintype "unspecified"))
    )
    (net (code "42") (name "Net-(U8-DIR)") (class "Default")
      (node (ref "R15") (pin "1") (pinfunction "1_1") (pintype "input"))
      (node (ref "U8") (pin "5") (pinfunction "DIR_5") (pintype "unspecified"))
    )
    (net (code "43") (name "Net-(U9-DIR)") (class "Default")
      (node (ref "R17") (pin "1") (pinfunction "1_1") (pintype "input"))
      (node (ref "U9") (pin "5") (pinfunction "DIR_5") (pintype "unspecified"))
    )
    (net (code "44") (name "Net-(U10-DIR)") (class "Default")
      (node (ref "R18") (pin "1") (pinfunction "1_1") (pintype "input"))
      (node (ref "U10") (pin "5") (pinfunction "DIR_5") (pintype "unspecified"))
    )
    (net (code "45") (name "USB_5V") (class "Default")
      (node (ref "C17") (pin "2") (pinfunction "2_2") (pintype "input"))
      (node (ref "R6") (pin "2") (pinfunction "2_2") (pintype "input"))
      (node (ref "TP2") (pin "1") (pinfunction "1_1") (pintype "input"))
      (node (ref "U2") (pin "6") (pinfunction "IN_6") (pintype "input"))
      (node (ref "USB1") (pin "11") (pinfunction "VBUS_11") (pintype "unspecified"))
      (node (ref "USB1") (pin "2") (pinfunction "VBUS_2") (pintype "unspecified"))
    )
    (net (code "46") (name "VCORE") (class "Default")
      (node (ref "C10") (pin "2") (pinfunction "2_2") (pintype "input"))
      (node (ref "C11") (pin "2") (pinfunction "2_2") (pintype "input"))
      (node (ref "C12") (pin "2") (pinfunction "2_2") (pintype "input"))
      (node (ref "C13") (pin "1") (pinfunction "1_1") (pintype "input"))
      (node (ref "TP1") (pin "1") (pinfunction "1_1") (pintype "input"))
      (node (ref "U1") (pin "12") (pinfunction "VCORE_12") (pintype "input"))
      (node (ref "U1") (pin "37") (pinfunction "VCORE_37") (pintype "input"))
      (node (ref "U1") (pin "49") (pinfunction "VREGOUT_49") (pintype "input"))
      (node (ref "U1") (pin "64") (pinfunction "VCORE_64") (pintype "input"))
    )
    (net (code "47") (name "VREF_CONN") (class "Default")
      (node (ref "C21") (pin "2") (pinfunction "2_2") (pintype "input"))
      (node (ref "C22") (pin "2") (pinfunction "2_2") (pintype "input"))
      (node (ref "C24") (pin "2") (pinfunction "2_2") (pintype "input"))
      (node (ref "C26") (pin "2") (pinfunction "2_2") (pintype "input"))
      (node (ref "C28") (pin "2") (pinfunction "2_2") (pintype "input"))
      (node (ref "C30") (pin "2") (pinfunction "2_2") (pintype "input"))
      (node (ref "C9") (pin "2") (pinfunction "2_2") (pintype "input"))
      (node (ref "D7") (pin "2") (pinfunction "A_2") (pintype "unspecified"))
      (node (ref "H1") (pin "4") (pinfunction "4_4") (pintype "unspecified"))
      (node (ref "Q1") (pin "1") (pinfunction "G_1") (pintype "unspecified"))
      (node (ref "R20") (pin "2") (pinfunction "2_2") (pintype "input"))
      (node (ref "U10") (pin "6") (pinfunction "VCCB_6") (pintype "unspecified"))
      (node (ref "U5") (pin "6") (pinfunction "VCCB_6") (pintype "unspecified"))
      (node (ref "U6") (pin "6") (pinfunction "VCCB_6") (pintype "unspecified"))
      (node (ref "U7") (pin "6") (pinfunction "VCCB_6") (pintype "unspecified"))
      (node (ref "U8") (pin "6") (pinfunction "VCCB_6") (pintype "unspecified"))
      (node (ref "U9") (pin "6") (pinfunction "VCCB_6") (pintype "unspecified"))
    )
    (net (code "48") (name "unconnected-(H1-Pad6)") (class "Default")
      (node (ref "H1") (pin "6") (pinfunction "6_6") (pintype "unspecified+no_connect"))
    )
    (net (code "49") (name "unconnected-(H1-Pad7)") (class "Default")
      (node (ref "H1") (pin "7") (pinfunction "7_7") (pintype "unspecified+no_connect"))
    )
    (net (code "50") (name "unconnected-(H1-Pad8)") (class "Default")
      (node (ref "H1") (pin "8") (pinfunction "8_8") (pintype "unspecified+no_connect"))
    )
    (net (code "51") (name "unconnected-(U1-ACBUS0-Pad26)") (class "Default")
      (node (ref "U1") (pin "26") (pinfunction "ACBUS0_26") (pintype "input+no_connect"))
    )
    (net (code "52") (name "unconnected-(U1-ACBUS1-Pad27)") (class "Default")
      (node (ref "U1") (pin "27") (pinfunction "ACBUS1_27") (pintype "input+no_connect"))
    )
    (net (code "53") (name "unconnected-(U1-ACBUS2-Pad28)") (class "Default")
      (node (ref "U1") (pin "28") (pinfunction "ACBUS2_28") (pintype "input+no_connect"))
    )
    (net (code "54") (name "unconnected-(U1-ACBUS3-Pad29)") (class "Default")
      (node (ref "U1") (pin "29") (pinfunction "ACBUS3_29") (pintype "input+no_connect"))
    )
    (net (code "55") (name "unconnected-(U1-ACBUS4-Pad30)") (class "Default")
      (node (ref "U1") (pin "30") (pinfunction "ACBUS4_30") (pintype "input+no_connect"))
    )
    (net (code "56") (name "unconnected-(U1-ACBUS5-Pad32)") (class "Default")
      (node (ref "U1") (pin "32") (pinfunction "ACBUS5_32") (pintype "input+no_connect"))
    )
    (net (code "57") (name "unconnected-(U1-ACBUS6-Pad33)") (class "Default")
      (node (ref "U1") (pin "33") (pinfunction "ACBUS6_33") (pintype "input+no_connect"))
    )
    (net (code "58") (name "unconnected-(U1-ACBUS7-Pad34)") (class "Default")
      (node (ref "U1") (pin "34") (pinfunction "ACBUS7_34") (pintype "input+no_connect"))
    )
    (net (code "59") (name "unconnected-(U1-ADBUS4-Pad21)") (class "Default")
      (node (ref "U1") (pin "21") (pinfunction "ADBUS4_21") (pintype "input+no_connect"))
    )
    (net (code "60") (name "unconnected-(U1-ADBUS5-Pad22)") (class "Default")
      (node (ref "U1") (pin "22") (pinfunction "ADBUS5_22") (pintype "input+no_connect"))
    )
    (net (code "61") (name "unconnected-(U1-ADBUS6-Pad23)") (class "Default")
      (node (ref "U1") (pin "23") (pinfunction "ADBUS6_23") (pintype "input+no_connect"))
    )
    (net (code "62") (name "unconnected-(U1-ADBUS7-Pad24)") (class "Default")
      (node (ref "U1") (pin "24") (pinfunction "ADBUS7_24") (pintype "input+no_connect"))
    )
    (net (code "63") (name "unconnected-(U1-BCBUS0-Pad48)") (class "Default")
      (node (ref "U1") (pin "48") (pinfunction "BCBUS0_48") (pintype "input+no_connect"))
    )
    (net (code "64") (name "unconnected-(U1-BCBUS1-Pad52)") (class "Default")
      (node (ref "U1") (pin "52") (pinfunction "BCBUS1_52") (pintype "input+no_connect"))
    )
    (net (code "65") (name "unconnected-(U1-BCBUS2-Pad53)") (class "Default")
      (node (ref "U1") (pin "53") (pinfunction "BCBUS2_53") (pintype "input+no_connect"))
    )
    (net (code "66") (name "unconnected-(U1-BCBUS5-Pad57)") (class "Default")
      (node (ref "U1") (pin "57") (pinfunction "BCBUS5_57") (pintype "input+no_connect"))
    )
    (net (code "67") (name "unconnected-(U1-BCBUS6-Pad58)") (class "Default")
      (node (ref "U1") (pin "58") (pinfunction "BCBUS6_58") (pintype "input+no_connect"))
    )
    (net (code "68") (name "unconnected-(U1-BCBUS7-Pad59)") (class "Default")
      (node (ref "U1") (pin "59") (pinfunction "BCBUS7_59") (pintype "input+no_connect"))
    )
    (net (code "69") (name "unconnected-(U1-BDBUS2-Pad40)") (class "Default")
      (node (ref "U1") (pin "40") (pinfunction "BDBUS2_40") (pintype "input+no_connect"))
    )
    (net (code "70") (name "unconnected-(U1-BDBUS3-Pad41)") (class "Default")
      (node (ref "U1") (pin "41") (pinfunction "BDBUS3_41") (pintype "input+no_connect"))
    )
    (net (code "71") (name "unconnected-(U1-BDBUS4-Pad43)") (class "Default")
      (node (ref "U1") (pin "43") (pinfunction "BDBUS4_43") (pintype "input+no_connect"))
    )
    (net (code "72") (name "unconnected-(U1-BDBUS5-Pad44)") (class "Default")
      (node (ref "U1") (pin "44") (pinfunction "BDBUS5_44") (pintype "input+no_connect"))
    )
    (net (code "73") (name "unconnected-(U1-BDBUS6-Pad45)") (class "Default")
      (node (ref "U1") (pin "45") (pinfunction "BDBUS6_45") (pintype "input+no_connect"))
    )
    (net (code "74") (name "unconnected-(U1-BDBUS7-Pad46)") (class "Default")
      (node (ref "U1") (pin "46") (pinfunction "BDBUS7_46") (pintype "input+no_connect"))
    )
    (net (code "75") (name "unconnected-(U1-PWREN#-Pad60)") (class "Default")
      (node (ref "U1") (pin "60") (pinfunction "PWREN#_60") (pintype "input+no_connect"))
    )
    (net (code "76") (name "unconnected-(U1-SUSPEND#-Pad36)") (class "Default")
      (node (ref "U1") (pin "36") (pinfunction "SUSPEND#_36") (pintype "input+no_connect"))
    )
    (net (code "77") (name "unconnected-(U2-FAULT#-Pad3)") (class "Default")
      (node (ref "U2") (pin "3") (pinfunction "FAULT#_3") (pintype "input+no_connect"))
    )
    (net (code "78") (name "unconnected-(U3-NC-Pad4)") (class "Default")
      (node (ref "U3") (pin "4") (pinfunction "NC_4") (pintype "input+no_connect"))
    )
    (net (code "79") (name "unconnected-(USB1-SBU1-Pad9)") (class "Default")
      (node (ref "USB1") (pin "9") (pinfunction "SBU1_9") (pintype "unspecified+no_connect"))
    )
    (net (code "80") (name "unconnected-(USB1-SBU2-Pad3)") (class "Default")
      (node (ref "USB1") (pin "3") (pinfunction "SBU2_3") (pintype "unspecified+no_connect"))
    )
  )
)
